# TugasAkhir.net
KiCad netlist of a schematic drawn in EAGLE
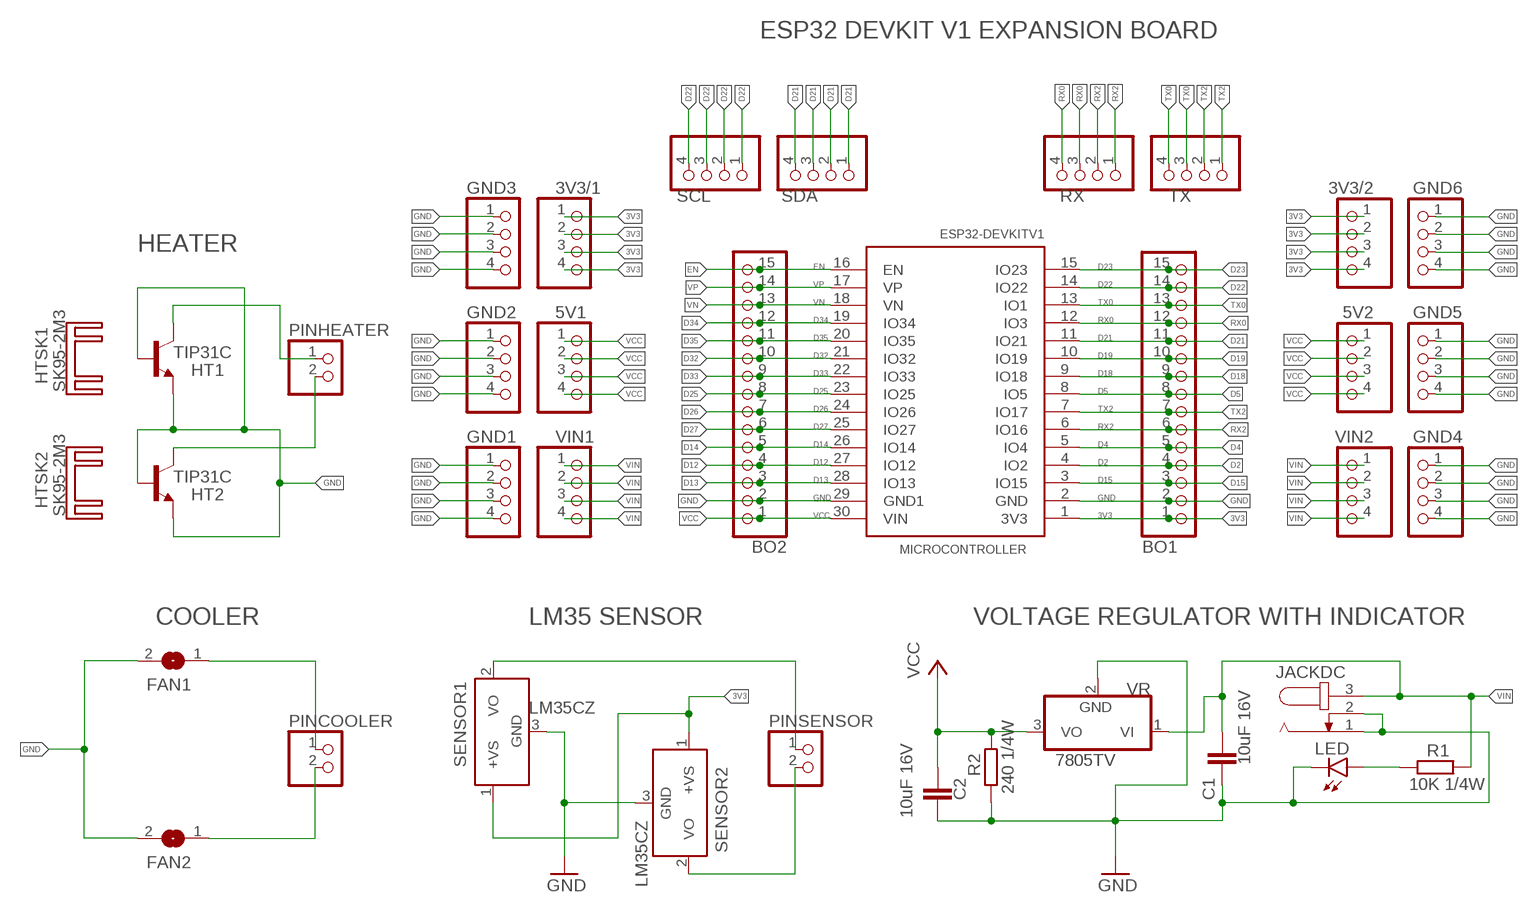
[diagram p0: schematic, sheet 1]

(export (version "E")
  (design (tool "Eeschema 10.0.6"))
  (components
    (comp (ref "3V3/1")
      (value "PINHD-1X4")
      (footprint "eagle-import:1X04")
      (libsource (lib "eagle-import") (part "PINHD-1X4"))
    )
    (comp (ref "3V3/2")
      (value "PINHD-1X4")
      (footprint "eagle-import:1X04")
      (libsource (lib "eagle-import") (part "PINHD-1X4"))
    )
    (comp (ref "5V1")
      (value "PINHD-1X4")
      (footprint "eagle-import:1X04")
      (libsource (lib "eagle-import") (part "PINHD-1X4"))
    )
    (comp (ref "5V2")
      (value "PINHD-1X4")
      (footprint "eagle-import:1X04")
      (libsource (lib "eagle-import") (part "PINHD-1X4"))
    )
    (comp (ref "BO1")
      (value "PINHD-1X15")
      (footprint "eagle-import:1X15")
      (libsource (lib "eagle-import") (part "PINHD-1X15"))
    )
    (comp (ref "BO2")
      (value "PINHD-1X15")
      (footprint "eagle-import:1X15")
      (libsource (lib "eagle-import") (part "PINHD-1X15"))
    )
    (comp (ref "C1")
      (value "10uF 16V")
      (footprint "eagle-import:C1206K")
      (libsource (lib "eagle-import") (part "C-EUC1206K"))
    )
    (comp (ref "C2")
      (value "10uF 16V")
      (footprint "eagle-import:C1206K")
      (libsource (lib "eagle-import") (part "C-EUC1206K"))
    )
    (comp (ref "FAN1")
      (value "SJW")
      (footprint "eagle-import:SJW")
      (libsource (lib "eagle-import") (part "SJW"))
    )
    (comp (ref "FAN2")
      (value "SJW")
      (footprint "eagle-import:SJW")
      (libsource (lib "eagle-import") (part "SJW"))
    )
    (comp (ref "GND1")
      (value "PINHD-1X4")
      (footprint "eagle-import:1X04")
      (libsource (lib "eagle-import") (part "PINHD-1X4"))
    )
    (comp (ref "GND2")
      (value "PINHD-1X4")
      (footprint "eagle-import:1X04")
      (libsource (lib "eagle-import") (part "PINHD-1X4"))
    )
    (comp (ref "GND3")
      (value "PINHD-1X4")
      (footprint "eagle-import:1X04")
      (libsource (lib "eagle-import") (part "PINHD-1X4"))
    )
    (comp (ref "GND4")
      (value "PINHD-1X4")
      (footprint "eagle-import:1X04")
      (libsource (lib "eagle-import") (part "PINHD-1X4"))
    )
    (comp (ref "GND5")
      (value "PINHD-1X4")
      (footprint "eagle-import:1X04")
      (libsource (lib "eagle-import") (part "PINHD-1X4"))
    )
    (comp (ref "GND6")
      (value "PINHD-1X4")
      (footprint "eagle-import:1X04")
      (libsource (lib "eagle-import") (part "PINHD-1X4"))
    )
    (comp (ref "HT1")
      (value "TIP31C")
      (footprint "eagle-import:TO220")
      (libsource (lib "eagle-import") (part "TIP31C"))
    )
    (comp (ref "HT2")
      (value "TIP31C")
      (footprint "eagle-import:TO220")
      (libsource (lib "eagle-import") (part "TIP31C"))
    )
    (comp (ref "HTSK1")
      (value "SK95-2M3")
      (footprint "eagle-import:SK95-2M3")
      (libsource (lib "eagle-import") (part "SK95-2M3"))
    )
    (comp (ref "HTSK2")
      (value "SK95-2M3")
      (footprint "eagle-import:SK95-2M3")
      (libsource (lib "eagle-import") (part "SK95-2M3"))
    )
    (comp (ref "JACKDC")
      (value "JACK-PLUG1")
      (footprint "eagle-import:SPC4078")
      (libsource (lib "eagle-import") (part "JACK-PLUG1"))
    )
    (comp (ref "LED")
      (value "LEDB155")
      (footprint "eagle-import:Q62902-B155")
      (libsource (lib "eagle-import") (part "LEDB155"))
    )
    (comp (ref "MICROCONTROLLER")
      (value "ESP32DEVKITV1")
      (footprint "eagle-import:ESP32-DEVKITV1")
      (libsource (lib "eagle-import") (part "ESP32DEVKITV1"))
    )
    (comp (ref "PINCOOLER")
      (value "PINHD-1X2")
      (footprint "eagle-import:1X02")
      (libsource (lib "eagle-import") (part "PINHD-1X2"))
    )
    (comp (ref "PINHEATER")
      (value "PINHD-1X2")
      (footprint "eagle-import:1X02")
      (libsource (lib "eagle-import") (part "PINHD-1X2"))
    )
    (comp (ref "PINSENSOR")
      (value "PINHD-1X2")
      (footprint "eagle-import:1X02")
      (libsource (lib "eagle-import") (part "PINHD-1X2"))
    )
    (comp (ref "R1")
      (value "10K 1/4W")
      (footprint "eagle-import:M1206")
      (libsource (lib "eagle-import") (part "R-EU_M1206"))
    )
    (comp (ref "R2")
      (value "240 1/4W")
      (footprint "eagle-import:M1206")
      (libsource (lib "eagle-import") (part "R-EU_M1206"))
    )
    (comp (ref "RX")
      (value "PINHD-1X4")
      (footprint "eagle-import:1X04")
      (libsource (lib "eagle-import") (part "PINHD-1X4"))
    )
    (comp (ref "SCL")
      (value "PINHD-1X4")
      (footprint "eagle-import:1X04")
      (libsource (lib "eagle-import") (part "PINHD-1X4"))
    )
    (comp (ref "SDA")
      (value "PINHD-1X4")
      (footprint "eagle-import:1X04")
      (libsource (lib "eagle-import") (part "PINHD-1X4"))
    )
    (comp (ref "SENSOR1")
      (value "LM35CZ")
      (footprint "eagle-import:TO92")
      (libsource (lib "eagle-import") (part "LM35CZ"))
    )
    (comp (ref "SENSOR2")
      (value "LM35CZ")
      (footprint "eagle-import:TO92")
      (libsource (lib "eagle-import") (part "LM35CZ"))
    )
    (comp (ref "TX")
      (value "PINHD-1X4")
      (footprint "eagle-import:1X04")
      (libsource (lib "eagle-import") (part "PINHD-1X4"))
    )
    (comp (ref "VIN1")
      (value "PINHD-1X4")
      (footprint "eagle-import:1X04")
      (libsource (lib "eagle-import") (part "PINHD-1X4"))
    )
    (comp (ref "VIN2")
      (value "PINHD-1X4")
      (footprint "eagle-import:1X04")
      (libsource (lib "eagle-import") (part "PINHD-1X4"))
    )
    (comp (ref "VR")
      (value "7805TV")
      (footprint "eagle-import:TO220V")
      (libsource (lib "eagle-import") (part "78TV05"))
    )
  )
  (nets
    (net (code "1") (name "3V3") (class "Default")
      (node (ref "3V3/1") (pin "1") (pinfunction "1_1") (pintype "passive"))
      (node (ref "3V3/1") (pin "2") (pinfunction "2_2") (pintype "passive"))
      (node (ref "3V3/1") (pin "3") (pinfunction "3_3") (pintype "passive"))
      (node (ref "3V3/1") (pin "4") (pinfunction "4_4") (pintype "passive"))
      (node (ref "3V3/2") (pin "1") (pinfunction "1_1") (pintype "passive"))
      (node (ref "3V3/2") (pin "2") (pinfunction "2_2") (pintype "passive"))
      (node (ref "3V3/2") (pin "3") (pinfunction "3_3") (pintype "passive"))
      (node (ref "3V3/2") (pin "4") (pinfunction "4_4") (pintype "passive"))
      (node (ref "BO1") (pin "1") (pinfunction "1_1") (pintype "passive"))
      (node (ref "MICROCONTROLLER") (pin "1") (pinfunction "3V3_1") (pintype "bidirectional"))
      (node (ref "SENSOR1") (pin "1") (pinfunction "+VS_1") (pintype "input"))
      (node (ref "SENSOR2") (pin "1") (pinfunction "+VS_1") (pintype "input"))
    )
    (net (code "2") (name "D2") (class "Default")
      (node (ref "BO1") (pin "4") (pinfunction "4_4") (pintype "passive"))
      (node (ref "MICROCONTROLLER") (pin "4") (pinfunction "IO2_4") (pintype "bidirectional"))
    )
    (net (code "3") (name "D4") (class "Default")
      (node (ref "BO1") (pin "5") (pinfunction "5_5") (pintype "passive"))
      (node (ref "MICROCONTROLLER") (pin "5") (pinfunction "IO4_5") (pintype "bidirectional"))
    )
    (net (code "4") (name "D5") (class "Default")
      (node (ref "BO1") (pin "8") (pinfunction "8_8") (pintype "passive"))
      (node (ref "MICROCONTROLLER") (pin "8") (pinfunction "IO5_8") (pintype "bidirectional"))
    )
    (net (code "5") (name "D12") (class "Default")
      (node (ref "BO2") (pin "4") (pinfunction "4_4") (pintype "passive"))
      (node (ref "MICROCONTROLLER") (pin "27") (pinfunction "IO12_27") (pintype "bidirectional"))
    )
    (net (code "6") (name "D13") (class "Default")
      (node (ref "BO2") (pin "3") (pinfunction "3_3") (pintype "passive"))
      (node (ref "MICROCONTROLLER") (pin "28") (pinfunction "IO13_28") (pintype "bidirectional"))
    )
    (net (code "7") (name "D14") (class "Default")
      (node (ref "BO2") (pin "5") (pinfunction "5_5") (pintype "passive"))
      (node (ref "MICROCONTROLLER") (pin "26") (pinfunction "IO14_26") (pintype "bidirectional"))
    )
    (net (code "8") (name "D15") (class "Default")
      (node (ref "BO1") (pin "3") (pinfunction "3_3") (pintype "passive"))
      (node (ref "MICROCONTROLLER") (pin "3") (pinfunction "IO15_3") (pintype "bidirectional"))
    )
    (net (code "9") (name "D18") (class "Default")
      (node (ref "BO1") (pin "9") (pinfunction "9_9") (pintype "passive"))
      (node (ref "MICROCONTROLLER") (pin "9") (pinfunction "IO18_9") (pintype "bidirectional"))
    )
    (net (code "10") (name "D19") (class "Default")
      (node (ref "BO1") (pin "10") (pinfunction "10_10") (pintype "passive"))
      (node (ref "MICROCONTROLLER") (pin "10") (pinfunction "IO19_10") (pintype "bidirectional"))
    )
    (net (code "11") (name "D21") (class "Default")
      (node (ref "BO1") (pin "11") (pinfunction "11_11") (pintype "passive"))
      (node (ref "MICROCONTROLLER") (pin "11") (pinfunction "IO21_11") (pintype "bidirectional"))
      (node (ref "SDA") (pin "1") (pinfunction "1_1") (pintype "passive"))
      (node (ref "SDA") (pin "2") (pinfunction "2_2") (pintype "passive"))
      (node (ref "SDA") (pin "3") (pinfunction "3_3") (pintype "passive"))
      (node (ref "SDA") (pin "4") (pinfunction "4_4") (pintype "passive"))
    )
    (net (code "12") (name "D22") (class "Default")
      (node (ref "BO1") (pin "14") (pinfunction "14_14") (pintype "passive"))
      (node (ref "MICROCONTROLLER") (pin "14") (pinfunction "IO22_14") (pintype "bidirectional"))
      (node (ref "SCL") (pin "1") (pinfunction "1_1") (pintype "passive"))
      (node (ref "SCL") (pin "2") (pinfunction "2_2") (pintype "passive"))
      (node (ref "SCL") (pin "3") (pinfunction "3_3") (pintype "passive"))
      (node (ref "SCL") (pin "4") (pinfunction "4_4") (pintype "passive"))
    )
    (net (code "13") (name "D23") (class "Default")
      (node (ref "BO1") (pin "15") (pinfunction "15_15") (pintype "passive"))
      (node (ref "MICROCONTROLLER") (pin "15") (pinfunction "IO23_15") (pintype "bidirectional"))
    )
    (net (code "14") (name "D25") (class "Default")
      (node (ref "BO2") (pin "8") (pinfunction "8_8") (pintype "passive"))
      (node (ref "MICROCONTROLLER") (pin "23") (pinfunction "IO25_23") (pintype "bidirectional"))
    )
    (net (code "15") (name "D26") (class "Default")
      (node (ref "BO2") (pin "7") (pinfunction "7_7") (pintype "passive"))
      (node (ref "MICROCONTROLLER") (pin "24") (pinfunction "IO26_24") (pintype "bidirectional"))
    )
    (net (code "16") (name "D27") (class "Default")
      (node (ref "BO2") (pin "6") (pinfunction "6_6") (pintype "passive"))
      (node (ref "MICROCONTROLLER") (pin "25") (pinfunction "IO27_25") (pintype "bidirectional"))
    )
    (net (code "17") (name "D32") (class "Default")
      (node (ref "BO2") (pin "10") (pinfunction "10_10") (pintype "passive"))
      (node (ref "MICROCONTROLLER") (pin "21") (pinfunction "IO32_21") (pintype "bidirectional"))
    )
    (net (code "18") (name "D33") (class "Default")
      (node (ref "BO2") (pin "9") (pinfunction "9_9") (pintype "passive"))
      (node (ref "MICROCONTROLLER") (pin "22") (pinfunction "IO33_22") (pintype "bidirectional"))
    )
    (net (code "19") (name "D34") (class "Default")
      (node (ref "BO2") (pin "12") (pinfunction "12_12") (pintype "passive"))
      (node (ref "MICROCONTROLLER") (pin "19") (pinfunction "IO34_19") (pintype "bidirectional"))
    )
    (net (code "20") (name "D35") (class "Default")
      (node (ref "BO2") (pin "11") (pinfunction "11_11") (pintype "passive"))
      (node (ref "MICROCONTROLLER") (pin "20") (pinfunction "IO35_20") (pintype "bidirectional"))
    )
    (net (code "21") (name "EN") (class "Default")
      (node (ref "BO2") (pin "15") (pinfunction "15_15") (pintype "passive"))
      (node (ref "MICROCONTROLLER") (pin "16") (pinfunction "EN_16") (pintype "bidirectional"))
    )
    (net (code "22") (name "GND") (class "Default")
      (node (ref "BO1") (pin "2") (pinfunction "2_2") (pintype "passive"))
      (node (ref "BO2") (pin "2") (pinfunction "2_2") (pintype "passive"))
      (node (ref "C1") (pin "2") (pinfunction "2_2") (pintype "passive"))
      (node (ref "C2") (pin "2") (pinfunction "2_2") (pintype "passive"))
      (node (ref "FAN1") (pin "2") (pinfunction "2_2") (pintype "passive"))
      (node (ref "FAN2") (pin "2") (pinfunction "2_2") (pintype "passive"))
      (node (ref "GND1") (pin "1") (pinfunction "1_1") (pintype "passive"))
      (node (ref "GND1") (pin "2") (pinfunction "2_2") (pintype "passive"))
      (node (ref "GND1") (pin "3") (pinfunction "3_3") (pintype "passive"))
      (node (ref "GND1") (pin "4") (pinfunction "4_4") (pintype "passive"))
      (node (ref "GND2") (pin "1") (pinfunction "1_1") (pintype "passive"))
      (node (ref "GND2") (pin "2") (pinfunction "2_2") (pintype "passive"))
      (node (ref "GND2") (pin "3") (pinfunction "3_3") (pintype "passive"))
      (node (ref "GND2") (pin "4") (pinfunction "4_4") (pintype "passive"))
      (node (ref "GND3") (pin "1") (pinfunction "1_1") (pintype "passive"))
      (node (ref "GND3") (pin "2") (pinfunction "2_2") (pintype "passive"))
      (node (ref "GND3") (pin "3") (pinfunction "3_3") (pintype "passive"))
      (node (ref "GND3") (pin "4") (pinfunction "4_4") (pintype "passive"))
      (node (ref "GND4") (pin "1") (pinfunction "1_1") (pintype "passive"))
      (node (ref "GND4") (pin "2") (pinfunction "2_2") (pintype "passive"))
      (node (ref "GND4") (pin "3") (pinfunction "3_3") (pintype "passive"))
      (node (ref "GND4") (pin "4") (pinfunction "4_4") (pintype "passive"))
      (node (ref "GND5") (pin "1") (pinfunction "1_1") (pintype "passive"))
      (node (ref "GND5") (pin "2") (pinfunction "2_2") (pintype "passive"))
      (node (ref "GND5") (pin "3") (pinfunction "3_3") (pintype "passive"))
      (node (ref "GND5") (pin "4") (pinfunction "4_4") (pintype "passive"))
      (node (ref "GND6") (pin "1") (pinfunction "1_1") (pintype "passive"))
      (node (ref "GND6") (pin "2") (pinfunction "2_2") (pintype "passive"))
      (node (ref "GND6") (pin "3") (pinfunction "3_3") (pintype "passive"))
      (node (ref "GND6") (pin "4") (pinfunction "4_4") (pintype "passive"))
      (node (ref "HT1") (pin "1") (pinfunction "B_1") (pintype "passive"))
      (node (ref "HT1") (pin "3") (pinfunction "E_3") (pintype "passive"))
      (node (ref "HT2") (pin "1") (pinfunction "B_1") (pintype "passive"))
      (node (ref "HT2") (pin "3") (pinfunction "E_3") (pintype "passive"))
      (node (ref "JACKDC") (pin "1") (pinfunction "1_1") (pintype "passive"))
      (node (ref "JACKDC") (pin "2") (pinfunction "2_2") (pintype "passive"))
      (node (ref "LED") (pin "K") (pinfunction "C_K") (pintype "passive"))
      (node (ref "MICROCONTROLLER") (pin "2") (pinfunction "GND_2") (pintype "bidirectional"))
      (node (ref "MICROCONTROLLER") (pin "29") (pinfunction "GND1_29") (pintype "bidirectional"))
      (node (ref "R2") (pin "1") (pinfunction "1_1") (pintype "passive"))
      (node (ref "SENSOR1") (pin "3") (pinfunction "GND_3") (pintype "power_in"))
      (node (ref "SENSOR2") (pin "3") (pinfunction "GND_3") (pintype "power_in"))
      (node (ref "VR") (pin "2") (pinfunction "GND_2") (pintype "passive"))
    )
    (net (code "23") (name "Net-(FAN1-Pad1)") (class "Default")
      (node (ref "FAN1") (pin "1") (pinfunction "1_1") (pintype "passive"))
      (node (ref "PINCOOLER") (pin "1") (pinfunction "1_1") (pintype "passive"))
    )
    (net (code "24") (name "Net-(FAN2-Pad1)") (class "Default")
      (node (ref "FAN2") (pin "1") (pinfunction "1_1") (pintype "passive"))
      (node (ref "PINCOOLER") (pin "2") (pinfunction "2_2") (pintype "passive"))
    )
    (net (code "25") (name "Net-(HT1-C)") (class "Default")
      (node (ref "HT1") (pin "2") (pinfunction "C_2") (pintype "passive"))
      (node (ref "PINHEATER") (pin "1") (pinfunction "1_1") (pintype "passive"))
    )
    (net (code "26") (name "Net-(HT2-C)") (class "Default")
      (node (ref "HT2") (pin "2") (pinfunction "C_2") (pintype "passive"))
      (node (ref "PINHEATER") (pin "2") (pinfunction "2_2") (pintype "passive"))
    )
    (net (code "27") (name "Net-(LED-PadA)") (class "Default")
      (node (ref "LED") (pin "A") (pinfunction "A_A") (pintype "passive"))
      (node (ref "R1") (pin "1") (pinfunction "1_1") (pintype "passive"))
    )
    (net (code "28") (name "Net-(SENSOR1-VO)") (class "Default")
      (node (ref "PINSENSOR") (pin "1") (pinfunction "1_1") (pintype "passive"))
      (node (ref "SENSOR1") (pin "2") (pinfunction "VO_2") (pintype "input"))
    )
    (net (code "29") (name "Net-(SENSOR2-VO)") (class "Default")
      (node (ref "PINSENSOR") (pin "2") (pinfunction "2_2") (pintype "passive"))
      (node (ref "SENSOR2") (pin "2") (pinfunction "VO_2") (pintype "input"))
    )
    (net (code "30") (name "RX0") (class "Default")
      (node (ref "BO1") (pin "12") (pinfunction "12_12") (pintype "passive"))
      (node (ref "MICROCONTROLLER") (pin "12") (pinfunction "IO3_12") (pintype "bidirectional"))
      (node (ref "RX") (pin "3") (pinfunction "3_3") (pintype "passive"))
      (node (ref "RX") (pin "4") (pinfunction "4_4") (pintype "passive"))
    )
    (net (code "31") (name "RX2") (class "Default")
      (node (ref "BO1") (pin "6") (pinfunction "6_6") (pintype "passive"))
      (node (ref "MICROCONTROLLER") (pin "6") (pinfunction "IO16_6") (pintype "bidirectional"))
      (node (ref "RX") (pin "1") (pinfunction "1_1") (pintype "passive"))
      (node (ref "RX") (pin "2") (pinfunction "2_2") (pintype "passive"))
    )
    (net (code "32") (name "TX0") (class "Default")
      (node (ref "BO1") (pin "13") (pinfunction "13_13") (pintype "passive"))
      (node (ref "MICROCONTROLLER") (pin "13") (pinfunction "IO1_13") (pintype "bidirectional"))
      (node (ref "TX") (pin "3") (pinfunction "3_3") (pintype "passive"))
      (node (ref "TX") (pin "4") (pinfunction "4_4") (pintype "passive"))
    )
    (net (code "33") (name "TX2") (class "Default")
      (node (ref "BO1") (pin "7") (pinfunction "7_7") (pintype "passive"))
      (node (ref "MICROCONTROLLER") (pin "7") (pinfunction "IO17_7") (pintype "bidirectional"))
      (node (ref "TX") (pin "1") (pinfunction "1_1") (pintype "passive"))
      (node (ref "TX") (pin "2") (pinfunction "2_2") (pintype "passive"))
    )
    (net (code "34") (name "VCC") (class "Default")
      (node (ref "5V1") (pin "1") (pinfunction "1_1") (pintype "passive"))
      (node (ref "5V1") (pin "2") (pinfunction "2_2") (pintype "passive"))
      (node (ref "5V1") (pin "3") (pinfunction "3_3") (pintype "passive"))
      (node (ref "5V1") (pin "4") (pinfunction "4_4") (pintype "passive"))
      (node (ref "5V2") (pin "1") (pinfunction "1_1") (pintype "passive"))
      (node (ref "5V2") (pin "2") (pinfunction "2_2") (pintype "passive"))
      (node (ref "5V2") (pin "3") (pinfunction "3_3") (pintype "passive"))
      (node (ref "5V2") (pin "4") (pinfunction "4_4") (pintype "passive"))
      (node (ref "BO2") (pin "1") (pinfunction "1_1") (pintype "passive"))
      (node (ref "C2") (pin "1") (pinfunction "1_1") (pintype "passive"))
      (node (ref "MICROCONTROLLER") (pin "30") (pinfunction "VIN_30") (pintype "bidirectional"))
      (node (ref "R2") (pin "2") (pinfunction "2_2") (pintype "passive"))
      (node (ref "VR") (pin "3") (pinfunction "VO_3") (pintype "passive"))
    )
    (net (code "35") (name "VIN") (class "Default")
      (node (ref "C1") (pin "1") (pinfunction "1_1") (pintype "passive"))
      (node (ref "JACKDC") (pin "3") (pinfunction "3_3") (pintype "passive"))
      (node (ref "R1") (pin "2") (pinfunction "2_2") (pintype "passive"))
      (node (ref "VIN1") (pin "1") (pinfunction "1_1") (pintype "passive"))
      (node (ref "VIN1") (pin "2") (pinfunction "2_2") (pintype "passive"))
      (node (ref "VIN1") (pin "3") (pinfunction "3_3") (pintype "passive"))
      (node (ref "VIN1") (pin "4") (pinfunction "4_4") (pintype "passive"))
      (node (ref "VIN2") (pin "1") (pinfunction "1_1") (pintype "passive"))
      (node (ref "VIN2") (pin "2") (pinfunction "2_2") (pintype "passive"))
      (node (ref "VIN2") (pin "3") (pinfunction "3_3") (pintype "passive"))
      (node (ref "VIN2") (pin "4") (pinfunction "4_4") (pintype "passive"))
      (node (ref "VR") (pin "1") (pinfunction "VI_1") (pintype "input"))
    )
    (net (code "36") (name "VN") (class "Default")
      (node (ref "BO2") (pin "13") (pinfunction "13_13") (pintype "passive"))
      (node (ref "MICROCONTROLLER") (pin "18") (pinfunction "VN_18") (pintype "bidirectional"))
    )
    (net (code "37") (name "VP") (class "Default")
      (node (ref "BO2") (pin "14") (pinfunction "14_14") (pintype "passive"))
      (node (ref "MICROCONTROLLER") (pin "17") (pinfunction "VP_17") (pintype "bidirectional"))
    )
  )
)
